# Design-TSC.net
KiCad netlist of a schematic drawn in EAGLE
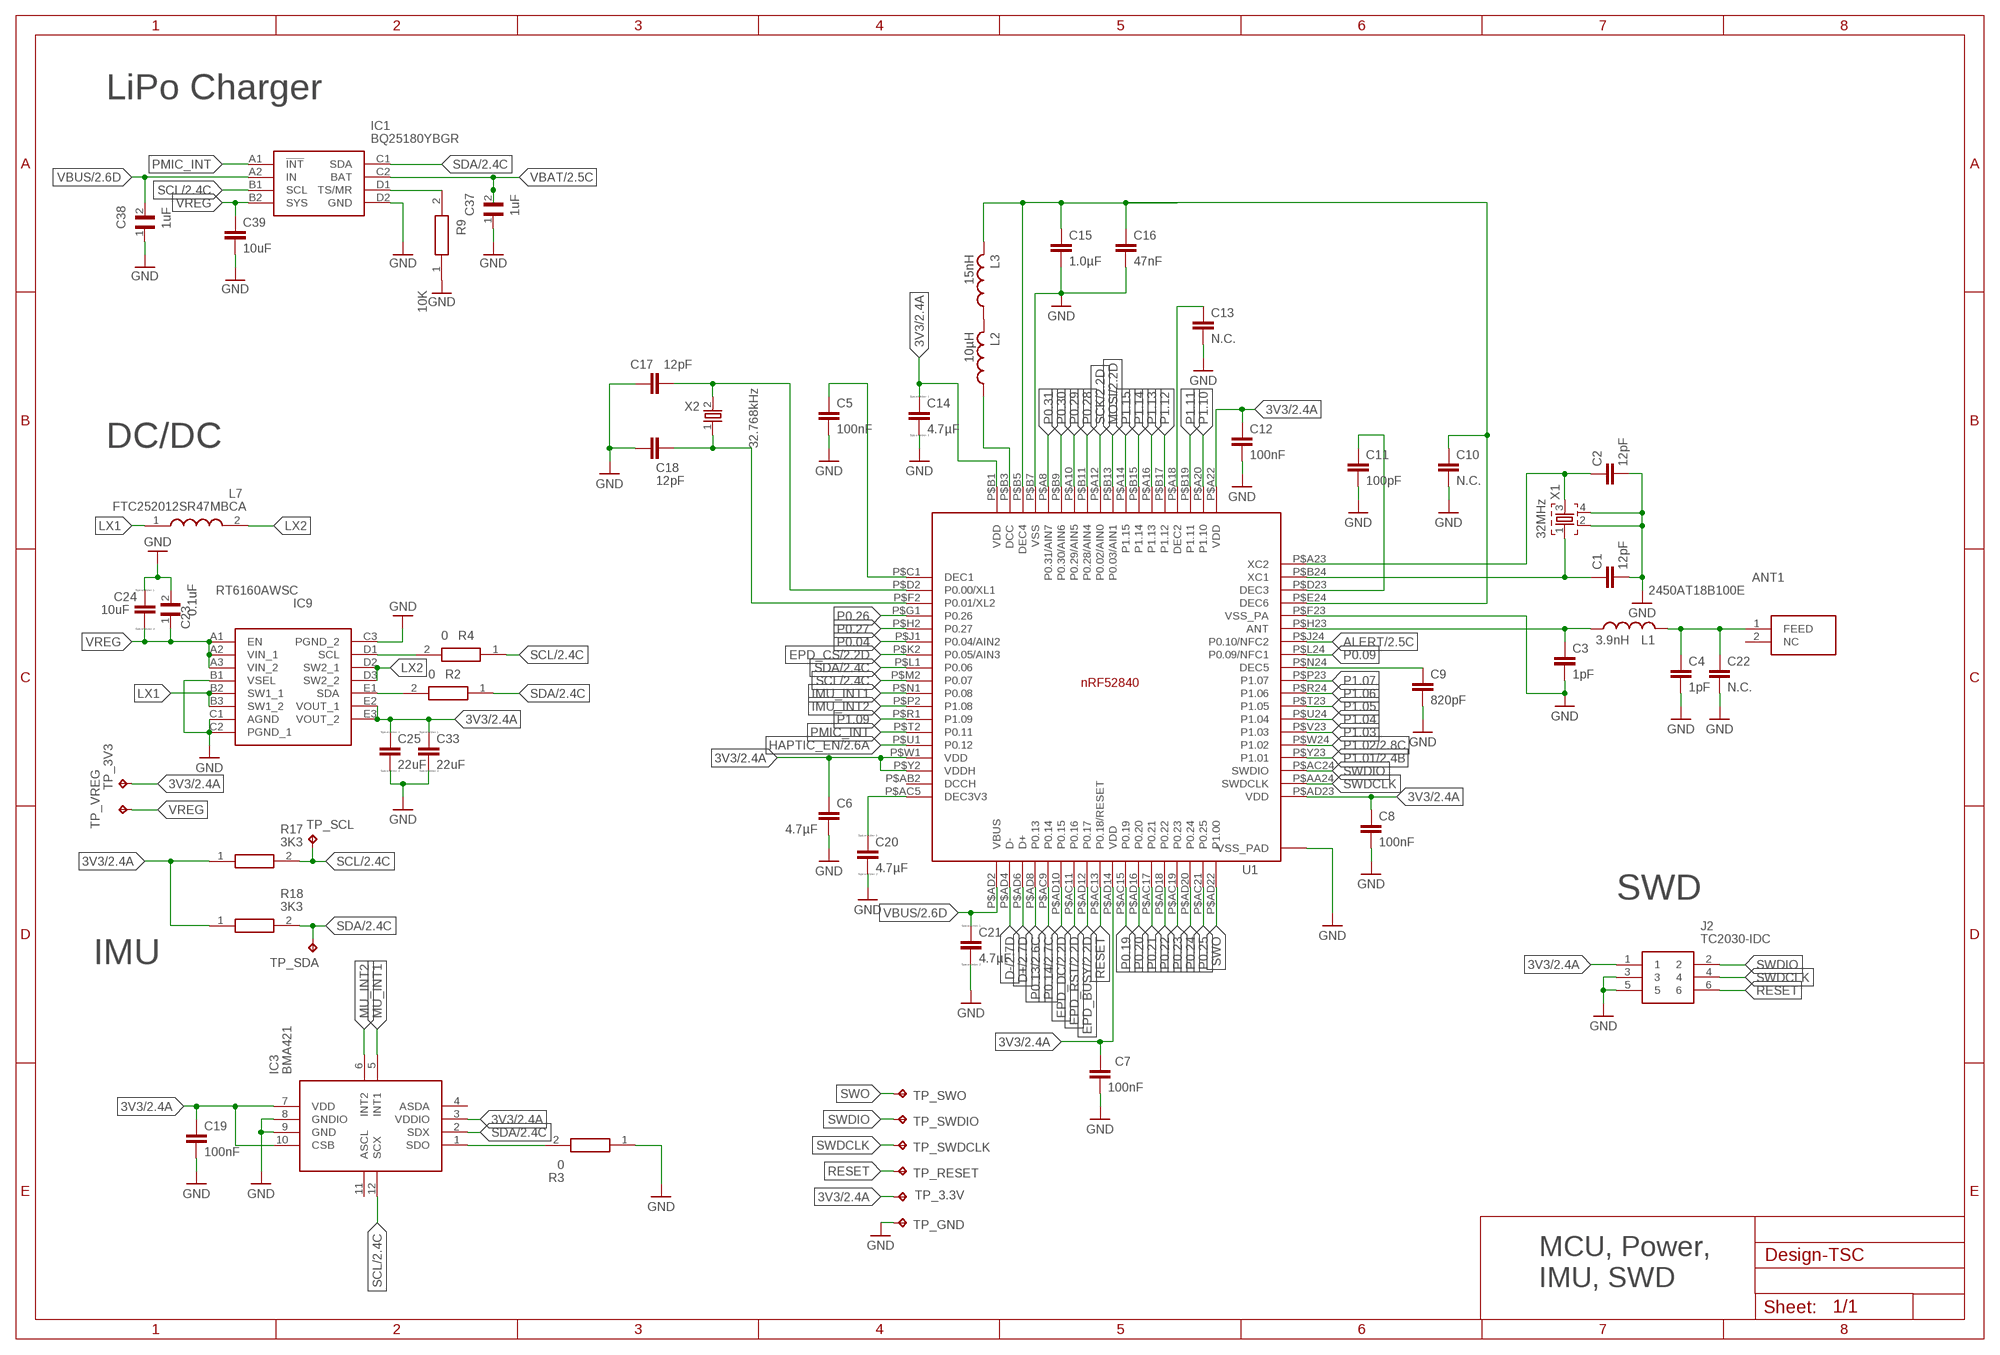
[diagram p0: schematic, sheet 1, part 1 of 2]
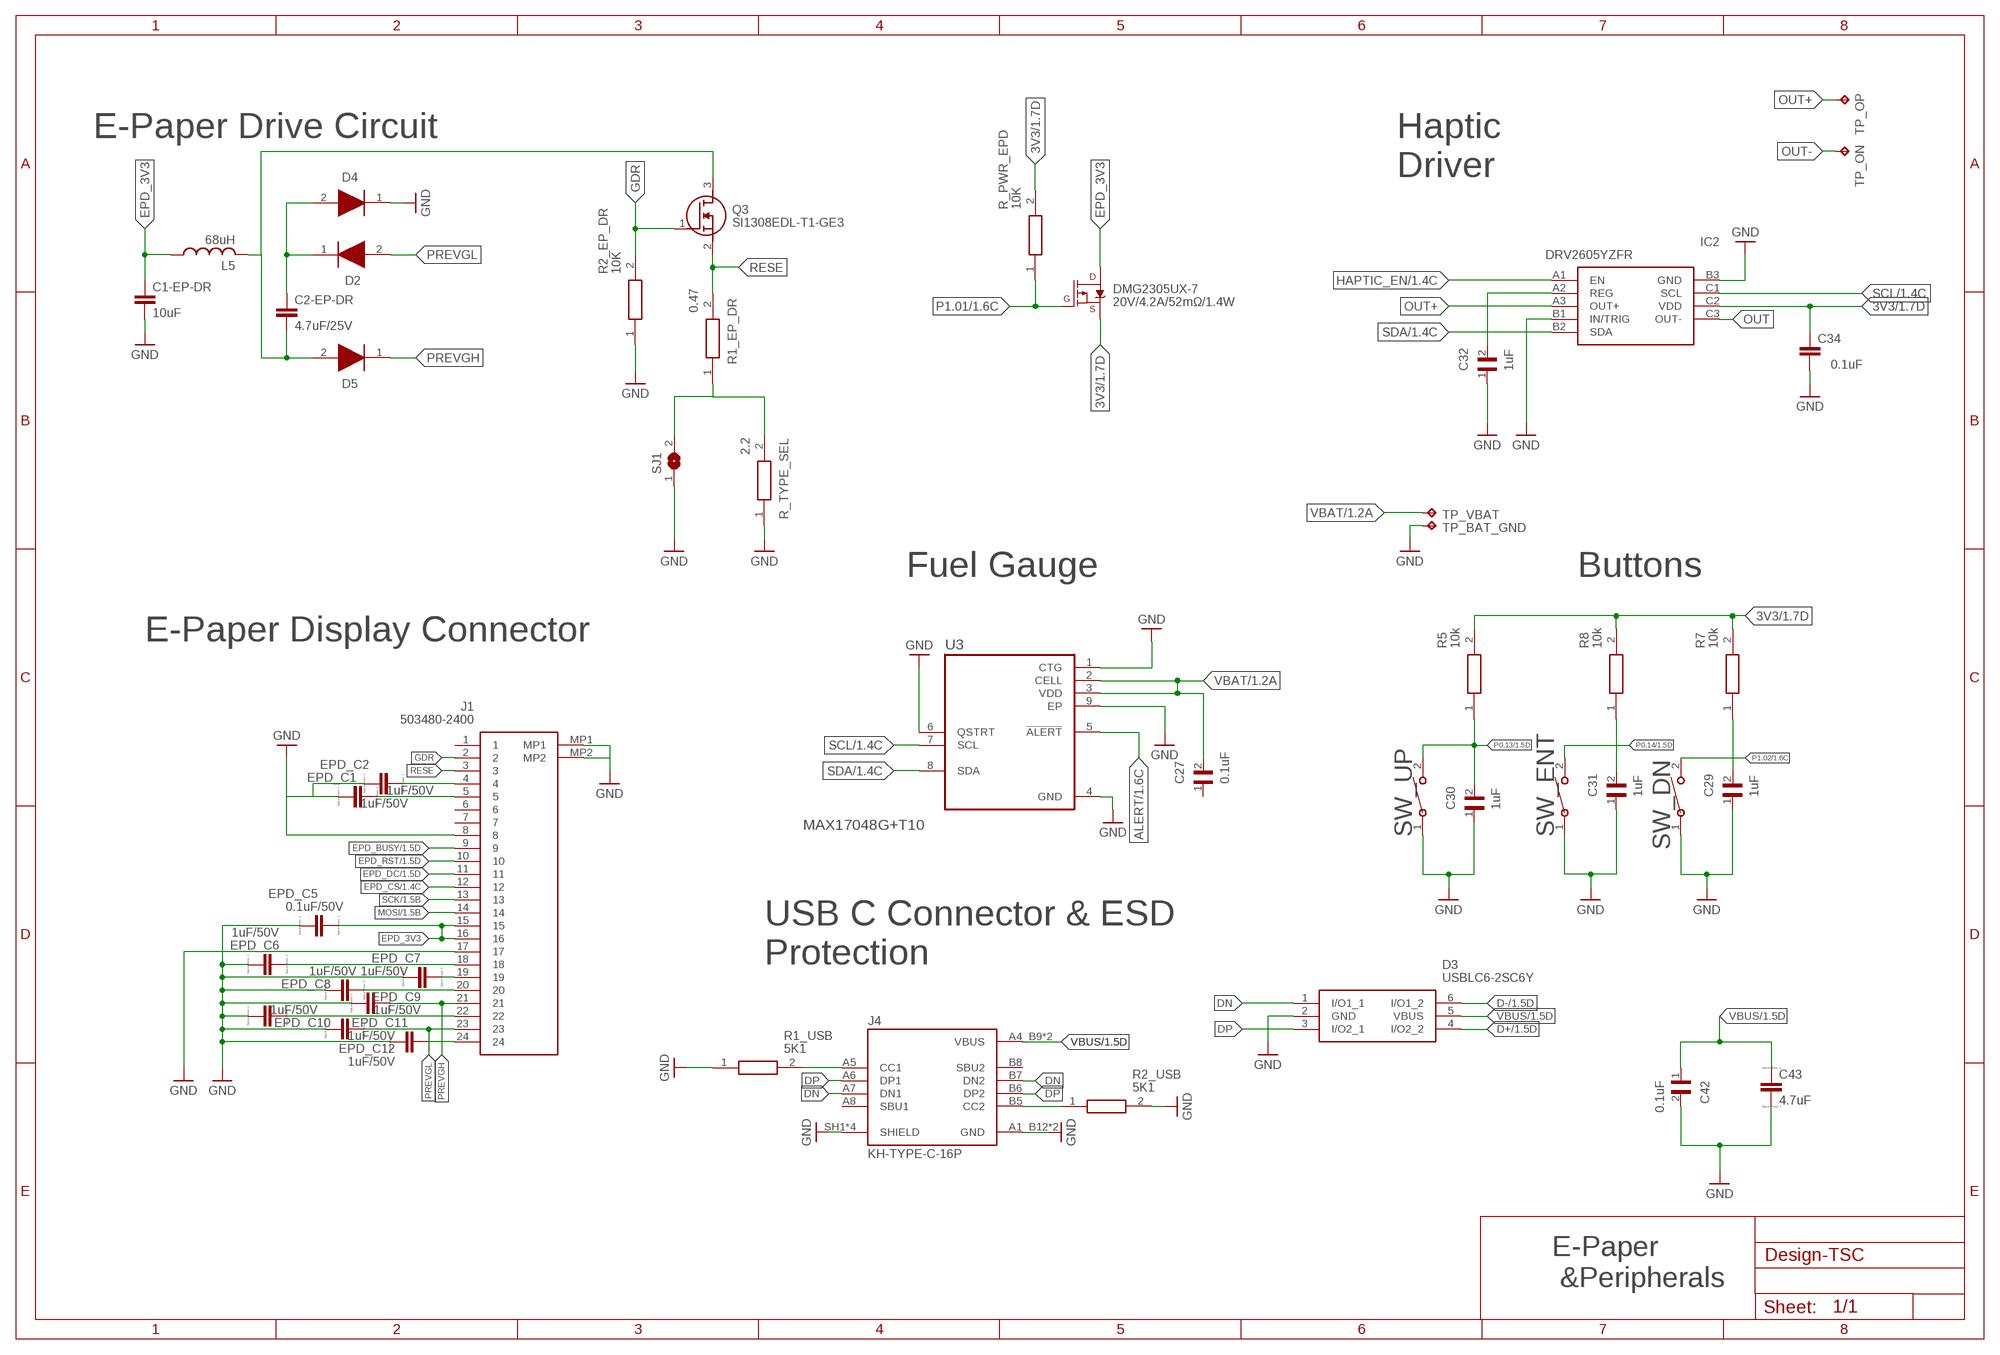
[diagram p1: schematic, sheet 1, part 2 of 2]

(export (version "E")
  (design (tool "Eeschema 10.0.6"))
  (components
    (comp (ref "ANT1")
      (value "2450AT18B100E")
      (footprint "eagle-import:2450AT18B100E_ANTC3216X140N")
      (fields (field (name "MOUSER_PART_NUMBER") "609-2450AT18B100E"))
      (libsource (lib "eagle-import") (part "2450AT18B100E_2450AT18B100E"))
    )
    (comp (ref "C1")
      (value "12pF")
      (footprint "eagle-import:NORDIC_NRF_3_RESC0201_L")
      (libsource (lib "eagle-import") (part "NORDIC_NRF_3_CAPACITOR_0201_L"))
    )
    (comp (ref "C1-EP-DR")
      (value "10uF")
      (footprint "eagle-import:NORDIC_NRF_3_RESC0201_L")
      (libsource (lib "eagle-import") (part "NORDIC_NRF_3_CAPACITOR_0201_L"))
    )
    (comp (ref "C2")
      (value "12pF")
      (footprint "eagle-import:NORDIC_NRF_3_RESC0201_L")
      (libsource (lib "eagle-import") (part "NORDIC_NRF_3_CAPACITOR_0201_L"))
    )
    (comp (ref "C2-EP-DR")
      (value "4.7uF/25V")
      (footprint "eagle-import:NORDIC_NRF_3_RESC0201_L")
      (libsource (lib "eagle-import") (part "NORDIC_NRF_3_CAPACITOR_0201_L"))
    )
    (comp (ref "C3")
      (value "1pF")
      (footprint "eagle-import:NORDIC_NRF_3_RESC0201_L")
      (libsource (lib "eagle-import") (part "NORDIC_NRF_3_CAPACITOR_0201_L"))
    )
    (comp (ref "C4")
      (value "1pF")
      (footprint "eagle-import:NORDIC_NRF_3_RESC0201_L")
      (libsource (lib "eagle-import") (part "NORDIC_NRF_3_CAPACITOR_0201_L"))
    )
    (comp (ref "C5")
      (value "100nF")
      (footprint "eagle-import:NORDIC_NRF_3_RESC0201_L")
      (libsource (lib "eagle-import") (part "NORDIC_NRF_3_CAPACITOR_0201_L"))
    )
    (comp (ref "C6")
      (value "4.7µF")
      (footprint "eagle-import:NORDIC_NRF_3_RESC0201_L")
      (libsource (lib "eagle-import") (part "NORDIC_NRF_3_CAPACITOR_0201_L"))
    )
    (comp (ref "C7")
      (value "100nF")
      (footprint "eagle-import:NORDIC_NRF_3_RESC0201_L")
      (libsource (lib "eagle-import") (part "NORDIC_NRF_3_CAPACITOR_0201_L"))
    )
    (comp (ref "C8")
      (value "100nF")
      (footprint "eagle-import:NORDIC_NRF_3_RESC0201_L")
      (libsource (lib "eagle-import") (part "NORDIC_NRF_3_CAPACITOR_0201_L"))
    )
    (comp (ref "C9")
      (value "820pF")
      (footprint "eagle-import:NORDIC_NRF_3_RESC0201_L")
      (libsource (lib "eagle-import") (part "NORDIC_NRF_3_CAPACITOR_0201_L"))
    )
    (comp (ref "C10")
      (value "N.C.")
      (footprint "eagle-import:NORDIC_NRF_3_RESC0201_L")
      (libsource (lib "eagle-import") (part "NORDIC_NRF_3_CAPACITOR_0201_L"))
    )
    (comp (ref "C11")
      (value "100pF")
      (footprint "eagle-import:NORDIC_NRF_3_RESC0201_L")
      (libsource (lib "eagle-import") (part "NORDIC_NRF_3_CAPACITOR_0201_L"))
    )
    (comp (ref "C12")
      (value "100nF")
      (footprint "eagle-import:NORDIC_NRF_3_RESC0201_L")
      (libsource (lib "eagle-import") (part "NORDIC_NRF_3_CAPACITOR_0201_L"))
    )
    (comp (ref "C13")
      (value "N.C.")
      (footprint "eagle-import:NORDIC_NRF_3_RESC0201_L")
      (libsource (lib "eagle-import") (part "NORDIC_NRF_3_CAPACITOR_0201_L"))
    )
    (comp (ref "C14")
      (value "4.7µF")
      (footprint "eagle-import:ESP32_C6_LIBRARY_1_ESP32_WROVER_EAGLE-LTSPICE_C0402")
      (libsource (lib "eagle-import") (part "ESP32_C6_LIBRARY_1_ESP32_WROVER_EAGLE-LTSPICE_CC0402"))
    )
    (comp (ref "C15")
      (value "1.0µF")
      (footprint "eagle-import:NORDIC_NRF_3_RESC0201_L")
      (libsource (lib "eagle-import") (part "NORDIC_NRF_3_CAPACITOR_0201_L"))
    )
    (comp (ref "C16")
      (value "47nF")
      (footprint "eagle-import:NORDIC_NRF_3_RESC0201_L")
      (libsource (lib "eagle-import") (part "NORDIC_NRF_3_CAPACITOR_0201_L"))
    )
    (comp (ref "C17")
      (value "12pF")
      (footprint "eagle-import:NORDIC_NRF_3_RESC0201_L")
      (libsource (lib "eagle-import") (part "NORDIC_NRF_3_CAPACITOR_0201_L"))
    )
    (comp (ref "C18")
      (value "12pF")
      (footprint "eagle-import:NORDIC_NRF_3_RESC0201_L")
      (libsource (lib "eagle-import") (part "NORDIC_NRF_3_CAPACITOR_0201_L"))
    )
    (comp (ref "C19")
      (value "100nF")
      (footprint "eagle-import:NORDIC_NRF_3_RESC0201_L")
      (libsource (lib "eagle-import") (part "NORDIC_NRF_3_CAPACITOR_0201_L"))
    )
    (comp (ref "C20")
      (value "4.7µF")
      (footprint "eagle-import:ESP32_C6_LIBRARY_1_ESP32_WROVER_EAGLE-LTSPICE_C0402")
      (libsource (lib "eagle-import") (part "ESP32_C6_LIBRARY_1_ESP32_WROVER_EAGLE-LTSPICE_CC0402"))
    )
    (comp (ref "C21")
      (value "4.7µF")
      (footprint "eagle-import:ESP32_C6_LIBRARY_1_ESP32_WROVER_EAGLE-LTSPICE_C0402")
      (libsource (lib "eagle-import") (part "ESP32_C6_LIBRARY_1_ESP32_WROVER_EAGLE-LTSPICE_CC0402"))
    )
    (comp (ref "C22")
      (value "N.C.")
      (footprint "eagle-import:NORDIC_NRF_3_RESC0201_L")
      (libsource (lib "eagle-import") (part "NORDIC_NRF_3_CAPACITOR_0201_L"))
    )
    (comp (ref "C23")
      (value "0.1uF")
      (footprint "eagle-import:GRM011R60J152KE01L_2_CAPC0201X13N")
      (fields (field (name "MF") "Murata") (field (name "MP") "GRM011R60J152KE01L"))
      (libsource (lib "eagle-import") (part "GRM011R60J152KE01L_2_GRM011R60J152KE01L"))
    )
    (comp (ref "C24")
      (value "10uF")
      (footprint "eagle-import:ESP32_C6_LIBRARY_1_ESP32_WROVER_EAGLE-LTSPICE_C0402")
      (libsource (lib "eagle-import") (part "ESP32_C6_LIBRARY_1_ESP32_WROVER_EAGLE-LTSPICE_CC0402"))
    )
    (comp (ref "C25")
      (value "22uF")
      (footprint "eagle-import:ESP32_C6_LIBRARY_1_ESP32_WROVER_EAGLE-LTSPICE_C0402")
      (libsource (lib "eagle-import") (part "ESP32_C6_LIBRARY_1_ESP32_WROVER_EAGLE-LTSPICE_CC0402"))
    )
    (comp (ref "C27")
      (value "0.1uF")
      (footprint "eagle-import:GRM011R60J152KE01L_2_CAPC0201X13N")
      (fields (field (name "MF") "Murata") (field (name "MP") "GRM011R60J152KE01L"))
      (libsource (lib "eagle-import") (part "GRM011R60J152KE01L_2_GRM011R60J152KE01L"))
    )
    (comp (ref "C29")
      (value "1uF")
      (footprint "eagle-import:GRM011R60J152KE01L_2_CAPC0201X13N")
      (fields (field (name "MF") "Murata") (field (name "MP") "GRM011R60J152KE01L"))
      (libsource (lib "eagle-import") (part "GRM011R60J152KE01L_2_GRM011R60J152KE01L"))
    )
    (comp (ref "C30")
      (value "1uF")
      (footprint "eagle-import:GRM011R60J152KE01L_2_CAPC0201X13N")
      (fields (field (name "MF") "Murata") (field (name "MP") "GRM011R60J152KE01L"))
      (libsource (lib "eagle-import") (part "GRM011R60J152KE01L_2_GRM011R60J152KE01L"))
    )
    (comp (ref "C31")
      (value "1uF")
      (footprint "eagle-import:GRM011R60J152KE01L_2_CAPC0201X13N")
      (fields (field (name "MF") "Murata") (field (name "MP") "GRM011R60J152KE01L"))
      (libsource (lib "eagle-import") (part "GRM011R60J152KE01L_2_GRM011R60J152KE01L"))
    )
    (comp (ref "C32")
      (value "1uF")
      (footprint "eagle-import:GRM011R60J152KE01L_2_CAPC0201X13N")
      (fields (field (name "MF") "Murata") (field (name "MP") "GRM011R60J152KE01L"))
      (libsource (lib "eagle-import") (part "GRM011R60J152KE01L_2_GRM011R60J152KE01L"))
    )
    (comp (ref "C33")
      (value "22uF")
      (footprint "eagle-import:ESP32_C6_LIBRARY_1_ESP32_WROVER_EAGLE-LTSPICE_C0402")
      (libsource (lib "eagle-import") (part "ESP32_C6_LIBRARY_1_ESP32_WROVER_EAGLE-LTSPICE_CC0402"))
    )
    (comp (ref "C34")
      (value "0.1uF")
      (footprint "eagle-import:NORDIC_NRF_3_RESC0201_L")
      (libsource (lib "eagle-import") (part "NORDIC_NRF_3_CAPACITOR_0201_L"))
    )
    (comp (ref "C37")
      (value "1uF")
      (footprint "eagle-import:GRM011R60J152KE01L_2_CAPC0201X13N")
      (fields (field (name "MF") "Murata") (field (name "MP") "GRM011R60J152KE01L"))
      (libsource (lib "eagle-import") (part "GRM011R60J152KE01L_2_GRM011R60J152KE01L"))
    )
    (comp (ref "C38")
      (value "1uF")
      (footprint "eagle-import:GRM011R60J152KE01L_2_CAPC0201X13N")
      (fields (field (name "MF") "Murata") (field (name "MP") "GRM011R60J152KE01L"))
      (libsource (lib "eagle-import") (part "GRM011R60J152KE01L_2_GRM011R60J152KE01L"))
    )
    (comp (ref "C39")
      (value "10uF")
      (footprint "eagle-import:NORDIC_NRF_3_RESC0201_L")
      (libsource (lib "eagle-import") (part "NORDIC_NRF_3_CAPACITOR_0201_L"))
    )
    (comp (ref "C42")
      (value "0.1uF")
      (footprint "eagle-import:GRM011R60J152KE01L_2_CAPC0201X13N")
      (fields (field (name "MF") "Murata") (field (name "MP") "GRM011R60J152KE01L"))
      (libsource (lib "eagle-import") (part "GRM011R60J152KE01L_2_GRM011R60J152KE01L"))
    )
    (comp (ref "C43")
      (value "4.7uF")
      (footprint "eagle-import:ESP32_C6_LIBRARY_1_ESP32_WROVER_EAGLE-LTSPICE_C0402")
      (libsource (lib "eagle-import") (part "ESP32_C6_LIBRARY_1_ESP32_WROVER_EAGLE-LTSPICE_CC0402"))
    )
    (comp (ref "D2")
      (value "ESP32_C6_LIBRARY_5_MBR0530")
      (footprint "eagle-import:ESP32_C6_LIBRARY_5_SOD3716X135N")
      (fields (field (name "MF") "ON Semiconductor") (field (name "MP") "MBR0530"))
      (libsource (lib "eagle-import") (part "ESP32_C6_LIBRARY_5_MBR0530"))
    )
    (comp (ref "D3")
      (value "USBLC6-2SC6Y")
      (footprint "eagle-import:ESP32_C6_LIBRARY_3_SOT95P280X145-6N")
      (fields (field (name "MF") "STMicroelectronics"))
      (libsource (lib "eagle-import") (part "ESP32_C6_LIBRARY_3_USBLC6-2SC6Y"))
    )
    (comp (ref "D4")
      (value "ESP32_C6_LIBRARY_5_MBR0530")
      (footprint "eagle-import:ESP32_C6_LIBRARY_5_SOD3716X135N")
      (fields (field (name "MF") "ON Semiconductor") (field (name "MP") "MBR0530"))
      (libsource (lib "eagle-import") (part "ESP32_C6_LIBRARY_5_MBR0530"))
    )
    (comp (ref "D5")
      (value "ESP32_C6_LIBRARY_5_MBR0530")
      (footprint "eagle-import:ESP32_C6_LIBRARY_5_SOD3716X135N")
      (fields (field (name "MF") "ON Semiconductor") (field (name "MP") "MBR0530"))
      (libsource (lib "eagle-import") (part "ESP32_C6_LIBRARY_5_MBR0530"))
    )
    (comp (ref "DMG2305UX-7")
      (value "20V/4.2A/52mΩ/1.4W")
      (footprint "eagle-import:ESP32_C6_LIBRARY_4_ESP32_C6_LIBRARY_4_ESP32_C6_LIBRARY_4_ESP32_C6_LIBRARY_4_ESP32_WROVER_SPARKFUN-DISCRETESEMI_SOT23-3")
      (libsource (lib "eagle-import") (part "ESP32_C6_LIBRARY_4_ESP32_WROVER_SPARKFUN-DISCRETESEMI_MOSFET_PCH-DMG2305UX-7"))
    )
    (comp (ref "EPD_C1")
      (value "1uF/50V")
      (footprint "eagle-import:ESP32_C6_LIBRARY_1_ESP32_WROVER_EAGLE-LTSPICE_C0402")
      (libsource (lib "eagle-import") (part "ESP32_C6_LIBRARY_1_ESP32_WROVER_EAGLE-LTSPICE_CC0402"))
    )
    (comp (ref "EPD_C2")
      (value "1uF/50V")
      (footprint "eagle-import:ESP32_C6_LIBRARY_1_ESP32_WROVER_EAGLE-LTSPICE_C0402")
      (libsource (lib "eagle-import") (part "ESP32_C6_LIBRARY_1_ESP32_WROVER_EAGLE-LTSPICE_CC0402"))
    )
    (comp (ref "EPD_C5")
      (value "0.1uF/50V")
      (footprint "eagle-import:ESP32_C6_LIBRARY_1_ESP32_WROVER_EAGLE-LTSPICE_C0402")
      (libsource (lib "eagle-import") (part "ESP32_C6_LIBRARY_1_ESP32_WROVER_EAGLE-LTSPICE_CC0402"))
    )
    (comp (ref "EPD_C6")
      (value "1uF/50V")
      (footprint "eagle-import:ESP32_C6_LIBRARY_1_ESP32_WROVER_EAGLE-LTSPICE_C0402")
      (libsource (lib "eagle-import") (part "ESP32_C6_LIBRARY_1_ESP32_WROVER_EAGLE-LTSPICE_CC0402"))
    )
    (comp (ref "EPD_C7")
      (value "1uF/50V")
      (footprint "eagle-import:ESP32_C6_LIBRARY_1_ESP32_WROVER_EAGLE-LTSPICE_C0402")
      (libsource (lib "eagle-import") (part "ESP32_C6_LIBRARY_1_ESP32_WROVER_EAGLE-LTSPICE_CC0402"))
    )
    (comp (ref "EPD_C8")
      (value "1uF/50V")
      (footprint "eagle-import:ESP32_C6_LIBRARY_1_ESP32_WROVER_EAGLE-LTSPICE_C0402")
      (libsource (lib "eagle-import") (part "ESP32_C6_LIBRARY_1_ESP32_WROVER_EAGLE-LTSPICE_CC0402"))
    )
    (comp (ref "EPD_C9")
      (value "1uF/50V")
      (footprint "eagle-import:ESP32_C6_LIBRARY_1_ESP32_WROVER_EAGLE-LTSPICE_C0402")
      (libsource (lib "eagle-import") (part "ESP32_C6_LIBRARY_1_ESP32_WROVER_EAGLE-LTSPICE_CC0402"))
    )
    (comp (ref "EPD_C10")
      (value "1uF/50V")
      (footprint "eagle-import:ESP32_C6_LIBRARY_1_ESP32_WROVER_EAGLE-LTSPICE_C0402")
      (libsource (lib "eagle-import") (part "ESP32_C6_LIBRARY_1_ESP32_WROVER_EAGLE-LTSPICE_CC0402"))
    )
    (comp (ref "EPD_C11")
      (value "1uF/50V")
      (footprint "eagle-import:ESP32_C6_LIBRARY_1_ESP32_WROVER_EAGLE-LTSPICE_C0402")
      (libsource (lib "eagle-import") (part "ESP32_C6_LIBRARY_1_ESP32_WROVER_EAGLE-LTSPICE_CC0402"))
    )
    (comp (ref "EPD_C12")
      (value "1uF/50V")
      (footprint "eagle-import:ESP32_C6_LIBRARY_1_ESP32_WROVER_EAGLE-LTSPICE_C0402")
      (libsource (lib "eagle-import") (part "ESP32_C6_LIBRARY_1_ESP32_WROVER_EAGLE-LTSPICE_CC0402"))
    )
    (comp (ref "IC1")
      (value "BQ25180YBGR")
      (footprint "eagle-import:BQ25180YBGR_BGA8C40P2X4_100X155X50")
      (fields (field (name "MOUSER_PART_NUMBER") "595-BQ25180YBGR"))
      (libsource (lib "eagle-import") (part "BQ25180YBGR_BQ25180YBGR"))
    )
    (comp (ref "IC2")
      (value "DRV2605YZFR")
      (footprint "eagle-import:DRV2605YZFR_BGA9C50P3X3_144X144X62")
      (libsource (lib "eagle-import") (part "DRV2605YZFR_DRV2605YZFR"))
    )
    (comp (ref "IC3")
      (value "BMA421")
      (footprint "eagle-import:BMA423_BMA423")
      (fields (field (name "ARROW_PART_NUMBER") "BMA423") (field (name "MOUSER_PART_NUMBER") "262-BMA423"))
      (libsource (lib "eagle-import") (part "BMA423_BMA423"))
    )
    (comp (ref "IC9")
      (value "RT6160AWSC")
      (footprint "eagle-import:RT6160AWSC_BGA15C40P3X5_140X230X60")
      (fields (field (name "MOUSER_PART_NUMBER") "835-RT6160AWSC"))
      (libsource (lib "eagle-import") (part "RT6160AWSC_RT6160AWSC"))
    )
    (comp (ref "J1")
      (value "503480-2400")
      (footprint "eagle-import:503480-2400_5034802400")
      (fields (field (name "MOUSER_PART_NUMBER") "538-503480-2400"))
      (libsource (lib "eagle-import") (part "503480-2400_503480-2400"))
    )
    (comp (ref "J2")
      (value "TC2030-IDC")
      (footprint "eagle-import:TC2030-IDC_TC2030IDC")
      (libsource (lib "eagle-import") (part "TC2030-IDC_TC2030-IDC"))
    )
    (comp (ref "J4")
      (value "KH-TYPE-C-16P")
      (footprint "eagle-import:KH-TYPE-C-16P_KINGHELM_KH-TYPE-C-16P")
      (fields (field (name "MF") "kinghelm"))
      (libsource (lib "eagle-import") (part "KH-TYPE-C-16P_KH-TYPE-C-16P"))
    )
    (comp (ref "L1")
      (value "3.9nH")
      (footprint "eagle-import:NORDIC_NRF_2_RESC0402_L")
      (libsource (lib "eagle-import") (part "NORDIC_NRF_2_INDUCTOR_0402_L"))
    )
    (comp (ref "L2")
      (value "10µH")
      (footprint "eagle-import:NORDIC_NRF_2_RESC0402_L")
      (libsource (lib "eagle-import") (part "NORDIC_NRF_2_INDUCTOR_0402_L"))
    )
    (comp (ref "L3")
      (value "15nH")
      (footprint "eagle-import:NORDIC_NRF_2_RESC0402_L")
      (libsource (lib "eagle-import") (part "NORDIC_NRF_2_INDUCTOR_0402_L"))
    )
    (comp (ref "L5")
      (value "68uH")
      (footprint "eagle-import:NORDIC_NRF_2_RESC0402_L")
      (libsource (lib "eagle-import") (part "NORDIC_NRF_2_INDUCTOR_0402_L"))
    )
    (comp (ref "L7")
      (value "FTC252012SR47MBCA")
      (footprint "eagle-import:MLP2016SR47MT0S1_INDC2016X100N")
      (libsource (lib "eagle-import") (part "MLP2016SR47MT0S1_FTC252012SR47MBCA"))
    )
    (comp (ref "Q3")
      (value "SI1308EDL-T1-GE3")
      (footprint "eagle-import:ESP32_C6_LIBRARY_6_SOT65P210X110-3N")
      (fields (field (name "MF") "Vishay Siliconix"))
      (libsource (lib "eagle-import") (part "ESP32_C6_LIBRARY_6_SI1308EDL-T1-GE3"))
    )
    (comp (ref "R1_EP_DR")
      (value "0.47")
      (footprint "eagle-import:ERA-1AEB3401C_0201")
      (libsource (lib "eagle-import") (part "ERA-1AEB3401C_CPF0201D7K68C1"))
    )
    (comp (ref "R1_USB")
      (value "5K1")
      (footprint "eagle-import:CPF0201D7K68C1_0201")
      (libsource (lib "eagle-import") (part "CPF0201D7K68C1_CPF0201D7K68C1"))
    )
    (comp (ref "R2")
      (value "0")
      (footprint "eagle-import:CPF0201D7K68C1_0201")
      (libsource (lib "eagle-import") (part "CPF0201D7K68C1_CPF0201D7K68C1"))
    )
    (comp (ref "R2_EP_DR")
      (value "10K")
      (footprint "eagle-import:ERA-1AEB3401C_0201")
      (libsource (lib "eagle-import") (part "ERA-1AEB3401C_CPF0201D7K68C1"))
    )
    (comp (ref "R2_USB")
      (value "5K1")
      (footprint "eagle-import:ERA-1AEB3401C_0201")
      (libsource (lib "eagle-import") (part "ERA-1AEB3401C_CPF0201D7K68C1"))
    )
    (comp (ref "R3")
      (value "0")
      (footprint "eagle-import:ERA-1AEB3401C_0201")
      (libsource (lib "eagle-import") (part "ERA-1AEB3401C_CPF0201D7K68C1"))
    )
    (comp (ref "R4")
      (value "0")
      (footprint "eagle-import:CPF0201D7K68C1_0201")
      (libsource (lib "eagle-import") (part "CPF0201D7K68C1_CPF0201D7K68C1"))
    )
    (comp (ref "R5")
      (value "10k")
      (footprint "eagle-import:CPF0201D7K68C1_0201")
      (libsource (lib "eagle-import") (part "CPF0201D7K68C1_CPF0201D7K68C1"))
    )
    (comp (ref "R7")
      (value "10k")
      (footprint "eagle-import:CPF0201D7K68C1_0201")
      (libsource (lib "eagle-import") (part "CPF0201D7K68C1_CPF0201D7K68C1"))
    )
    (comp (ref "R8")
      (value "10k")
      (footprint "eagle-import:CPF0201D7K68C1_0201")
      (libsource (lib "eagle-import") (part "CPF0201D7K68C1_CPF0201D7K68C1"))
    )
    (comp (ref "R9")
      (value "10K")
      (footprint "eagle-import:ERA-1AEB3401C_0201")
      (libsource (lib "eagle-import") (part "ERA-1AEB3401C_CPF0201D7K68C1"))
    )
    (comp (ref "R17")
      (value "3K3")
      (footprint "eagle-import:CPF0201D7K68C1_0201")
      (libsource (lib "eagle-import") (part "CPF0201D7K68C1_CPF0201D7K68C1"))
    )
    (comp (ref "R18")
      (value "3K3")
      (footprint "eagle-import:CPF0201D7K68C1_0201")
      (libsource (lib "eagle-import") (part "CPF0201D7K68C1_CPF0201D7K68C1"))
    )
    (comp (ref "R_PWR_EPD")
      (value "10K")
      (footprint "eagle-import:CPF0201D7K68C1_0201")
      (libsource (lib "eagle-import") (part "CPF0201D7K68C1_CPF0201D7K68C1"))
    )
    (comp (ref "R_TYPE_SEL")
      (value "2.2")
      (footprint "eagle-import:ERA-1AEB3401C_0201")
      (libsource (lib "eagle-import") (part "ERA-1AEB3401C_CPF0201D7K68C1"))
    )
    (comp (ref "SJ1")
      (value "ESP32_C6_LIBRARY_7_JUMPER_SJ")
      (footprint "eagle-import:ESP32_C6_LIBRARY_7_JUMPER_SJ")
      (libsource (lib "eagle-import") (part "ESP32_C6_LIBRARY_7_JUMPER_SJ"))
    )
    (comp (ref "SW_DN")
      (value "2025-10-22_07-23-44_LIBRARY_EVP-AKE31ASW_EVP-AKE31A_PAN")
      (footprint "eagle-import:2025-10-22_07-23-44_LIBRARY_SW_EVP-AKE31A_PAN")
      (fields
        (field (name "MANUFACTURER_PART_NUMBER") "EVP-AKE31A")
        (field (name "COPYRIGHT") "Copyright (C) 2025 Ultra Librarian. All rights reserved.")
      )
      (libsource (lib "eagle-import") (part "2025-10-22_07-23-44_LIBRARY_EVP-AKE31ASW_EVP-AKE31A_PAN"))
    )
    (comp (ref "SW_ENT")
      (value "2025-10-22_07-23-44_LIBRARY_EVP-AKE31ASW_EVP-AKE31A_PAN")
      (footprint "eagle-import:2025-10-22_07-23-44_LIBRARY_SW_EVP-AKE31A_PAN")
      (fields
        (field (name "MANUFACTURER_PART_NUMBER") "EVP-AKE31A")
        (field (name "COPYRIGHT") "Copyright (C) 2025 Ultra Librarian. All rights reserved.")
      )
      (libsource (lib "eagle-import") (part "2025-10-22_07-23-44_LIBRARY_EVP-AKE31ASW_EVP-AKE31A_PAN"))
    )
    (comp (ref "SW_UP")
      (value "2025-10-22_07-23-44_LIBRARY_EVP-AKE31ASW_EVP-AKE31A_PAN")
      (footprint "eagle-import:2025-10-22_07-23-44_LIBRARY_SW_EVP-AKE31A_PAN")
      (fields
        (field (name "MANUFACTURER_PART_NUMBER") "EVP-AKE31A")
        (field (name "COPYRIGHT") "Copyright (C) 2025 Ultra Librarian. All rights reserved.")
      )
      (libsource (lib "eagle-import") (part "2025-10-22_07-23-44_LIBRARY_EVP-AKE31ASW_EVP-AKE31A_PAN"))
    )
    (comp (ref "TP_3.3V")
      (value "HECTOR_WATCH_1_TPTP20R")
      (footprint "eagle-import:HECTOR_WATCH_1_TP20R")
      (libsource (lib "eagle-import") (part "HECTOR_WATCH_1_TPTP20R"))
    )
    (comp (ref "TP_3V3")
      (value "HECTOR_WATCH_1_TPTP20R")
      (footprint "eagle-import:HECTOR_WATCH_1_TP20R")
      (libsource (lib "eagle-import") (part "HECTOR_WATCH_1_TPTP20R"))
    )
    (comp (ref "TP_BAT_GND")
      (value "HECTOR_WATCH_1_TPTP20R")
      (footprint "eagle-import:HECTOR_WATCH_1_TP20R")
      (libsource (lib "eagle-import") (part "HECTOR_WATCH_1_TPTP20R"))
    )
    (comp (ref "TP_GND")
      (value "HECTOR_WATCH_1_TPTP20R")
      (footprint "eagle-import:HECTOR_WATCH_1_TP20R")
      (libsource (lib "eagle-import") (part "HECTOR_WATCH_1_TPTP20R"))
    )
    (comp (ref "TP_ON")
      (value "HECTOR_WATCH_1_TPTP20R")
      (footprint "eagle-import:HECTOR_WATCH_1_TP20R")
      (libsource (lib "eagle-import") (part "HECTOR_WATCH_1_TPTP20R"))
    )
    (comp (ref "TP_OP")
      (value "HECTOR_WATCH_1_TPTP20R")
      (footprint "eagle-import:HECTOR_WATCH_1_TP20R")
      (libsource (lib "eagle-import") (part "HECTOR_WATCH_1_TPTP20R"))
    )
    (comp (ref "TP_RESET")
      (value "HECTOR_WATCH_1_TPTP20R")
      (footprint "eagle-import:HECTOR_WATCH_1_TP20R")
      (libsource (lib "eagle-import") (part "HECTOR_WATCH_1_TPTP20R"))
    )
    (comp (ref "TP_SCL")
      (value "HECTOR_WATCH_1_TPTP20R")
      (footprint "eagle-import:HECTOR_WATCH_1_TP20R")
      (libsource (lib "eagle-import") (part "HECTOR_WATCH_1_TPTP20R"))
    )
    (comp (ref "TP_SDA")
      (value "HECTOR_WATCH_1_TPTP20R")
      (footprint "eagle-import:HECTOR_WATCH_1_TP20R")
      (libsource (lib "eagle-import") (part "HECTOR_WATCH_1_TPTP20R"))
    )
    (comp (ref "TP_SWDCLK")
      (value "HECTOR_WATCH_1_TPTP20R")
      (footprint "eagle-import:HECTOR_WATCH_1_TP20R")
      (libsource (lib "eagle-import") (part "HECTOR_WATCH_1_TPTP20R"))
    )
    (comp (ref "TP_SWDIO")
      (value "HECTOR_WATCH_1_TPTP20R")
      (footprint "eagle-import:HECTOR_WATCH_1_TP20R")
      (libsource (lib "eagle-import") (part "HECTOR_WATCH_1_TPTP20R"))
    )
    (comp (ref "TP_SWO")
      (value "HECTOR_WATCH_1_TPTP20R")
      (footprint "eagle-import:HECTOR_WATCH_1_TP20R")
      (libsource (lib "eagle-import") (part "HECTOR_WATCH_1_TPTP20R"))
    )
    (comp (ref "TP_VBAT")
      (value "HECTOR_WATCH_1_TPTP20R")
      (footprint "eagle-import:HECTOR_WATCH_1_TP20R")
      (libsource (lib "eagle-import") (part "HECTOR_WATCH_1_TPTP20R"))
    )
    (comp (ref "TP_VREG")
      (value "HECTOR_WATCH_1_TPTP20R")
      (footprint "eagle-import:HECTOR_WATCH_1_TP20R")
      (libsource (lib "eagle-import") (part "HECTOR_WATCH_1_TPTP20R"))
    )
    (comp (ref "U1")
      (value "NRF52840_QF")
      (footprint "eagle-import:NORDIC_NRF_4_AQFN50P700X700X85_HS-74N")
      (libsource (lib "eagle-import") (part "NORDIC_NRF_4_NRF52840_QF"))
    )
    (comp (ref "U3")
      (value "MAX17048G+T10")
      (footprint "eagle-import:ESP32_C6_LIBRARY_SON50P200X200X80-9N")
      (fields (field (name "MF") "Analog Devices"))
      (libsource (lib "eagle-import") (part "ESP32_C6_LIBRARY_MAX17048G+T10"))
    )
    (comp (ref "X1")
      (value "32MHz")
      (footprint "eagle-import:NORDIC_NRF_BT-XTAL_2016_N")
      (libsource (lib "eagle-import") (part "NORDIC_NRF_XTAL_32MHZ"))
    )
    (comp (ref "X2")
      (value "32.768kHz")
      (footprint "eagle-import:NORDIC_NRF_1_XTAL_3215_N")
      (libsource (lib "eagle-import") (part "NORDIC_NRF_1_XTAL_32KHZ"))
    )
  )
  (nets
    (net (code "1") (name "3V3{slash}1.7D") (class "Default")
      (node (ref "C34") (pin "1") (pinfunction "1_1") (pintype "passive"))
      (node (ref "DMG2305UX-7") (pin "2") (pinfunction "S_2") (pintype "bidirectional"))
      (node (ref "IC2") (pin "C2") (pinfunction "VDD_C2") (pintype "bidirectional"))
      (node (ref "R5") (pin "2") (pinfunction "2_2") (pintype "bidirectional"))
      (node (ref "R7") (pin "2") (pinfunction "2_2") (pintype "bidirectional"))
      (node (ref "R8") (pin "2") (pinfunction "2_2") (pintype "bidirectional"))
      (node (ref "R_PWR_EPD") (pin "2") (pinfunction "2_2") (pintype "bidirectional"))
    )
    (net (code "2") (name "3V3{slash}2.4A") (class "Default")
      (node (ref "C12") (pin "1") (pinfunction "1_1") (pintype "passive"))
      (node (ref "C14") (pin "1") (pinfunction "1_1") (pintype "passive"))
      (node (ref "C19") (pin "1") (pinfunction "1_1") (pintype "passive"))
      (node (ref "C25") (pin "1") (pinfunction "1_1") (pintype "passive"))
      (node (ref "C33") (pin "1") (pinfunction "1_1") (pintype "passive"))
      (node (ref "C6") (pin "1") (pinfunction "1_1") (pintype "passive"))
      (node (ref "C7") (pin "1") (pinfunction "1_1") (pintype "passive"))
      (node (ref "C8") (pin "1") (pinfunction "1_1") (pintype "passive"))
      (node (ref "IC3") (pin "10") (pinfunction "CSB_10") (pintype "bidirectional"))
      (node (ref "IC3") (pin "3") (pinfunction "VDDIO_3") (pintype "bidirectional"))
      (node (ref "IC3") (pin "7") (pinfunction "VDD_7") (pintype "bidirectional"))
      (node (ref "IC9") (pin "E2") (pinfunction "VOUT_1_E2") (pintype "bidirectional"))
      (node (ref "IC9") (pin "E3") (pinfunction "VOUT_2_E3") (pintype "bidirectional"))
      (node (ref "J2") (pin "1") (pinfunction "1_1") (pintype "bidirectional"))
      (node (ref "R17") (pin "1") (pinfunction "1_1") (pintype "bidirectional"))
      (node (ref "R18") (pin "1") (pinfunction "1_1") (pintype "bidirectional"))
      (node (ref "TP_3.3V") (pin "TP") (pinfunction "TP_TP") (pintype "input"))
      (node (ref "TP_3V3") (pin "TP") (pinfunction "TP_TP") (pintype "input"))
      (node (ref "U1") (pin "P$A22") (pinfunction "VDD_P$A22") (pintype "power_in"))
      (node (ref "U1") (pin "P$AD14") (pinfunction "VDD_P$AD14") (pintype "power_in"))
      (node (ref "U1") (pin "P$AD23") (pinfunction "VDD_P$AD23") (pintype "power_in"))
      (node (ref "U1") (pin "P$B1") (pinfunction "VDD_P$B1") (pintype "power_in"))
      (node (ref "U1") (pin "P$W1") (pinfunction "VDD_P$W1") (pintype "power_in"))
      (node (ref "U1") (pin "P$Y2") (pinfunction "VDDH_P$Y2") (pintype "power_in"))
    )
    (net (code "3") (name "ALERT{slash}1.6C") (class "Default")
      (node (ref "U3") (pin "5") (pinfunction "~{ALERT}_5") (pintype "output"))
    )
    (net (code "4") (name "ALERT{slash}2.5C") (class "Default")
      (node (ref "U1") (pin "P$J24") (pinfunction "P0.10/NFC2_P$J24") (pintype "bidirectional"))
    )
    (net (code "5") (name "D+{slash}1.5D") (class "Default")
      (node (ref "D3") (pin "4") (pinfunction "I/O2_2_4") (pintype "bidirectional"))
    )
    (net (code "6") (name "D+{slash}2.7D") (class "Default")
      (node (ref "U1") (pin "P$AD6") (pinfunction "D+_P$AD6") (pintype "bidirectional"))
    )
    (net (code "7") (name "D-{slash}1.5D") (class "Default")
      (node (ref "D3") (pin "6") (pinfunction "I/O1_2_6") (pintype "bidirectional"))
    )
    (net (code "8") (name "D-{slash}2.7D") (class "Default")
      (node (ref "U1") (pin "P$AD4") (pinfunction "D-_P$AD4") (pintype "bidirectional"))
    )
    (net (code "9") (name "DN") (class "Default")
      (node (ref "D3") (pin "1") (pinfunction "I/O1_1_1") (pintype "bidirectional"))
      (node (ref "J4") (pin "A7") (pinfunction "DN1_A7") (pintype "bidirectional"))
      (node (ref "J4") (pin "B7") (pinfunction "DN2_B7") (pintype "bidirectional"))
    )
    (net (code "10") (name "DP") (class "Default")
      (node (ref "D3") (pin "3") (pinfunction "I/O2_1_3") (pintype "bidirectional"))
      (node (ref "J4") (pin "A6") (pinfunction "DP1_A6") (pintype "bidirectional"))
      (node (ref "J4") (pin "B6") (pinfunction "DP2_B6") (pintype "bidirectional"))
    )
    (net (code "11") (name "EPD_3V3") (class "Default")
      (node (ref "C1-EP-DR") (pin "1") (pinfunction "1_1") (pintype "passive"))
      (node (ref "DMG2305UX-7") (pin "3") (pinfunction "D_3") (pintype "bidirectional"))
      (node (ref "EPD_C5") (pin "2") (pinfunction "2_2") (pintype "passive"))
      (node (ref "J1") (pin "15") (pinfunction "15_15") (pintype "bidirectional"))
      (node (ref "J1") (pin "16") (pinfunction "16_16") (pintype "bidirectional"))
      (node (ref "L5") (pin "1") (pinfunction "1_1") (pintype "passive"))
    )
    (net (code "12") (name "EPD_BUSY{slash}1.5D") (class "Default")
      (node (ref "J1") (pin "9") (pinfunction "9_9") (pintype "bidirectional"))
    )
    (net (code "13") (name "EPD_BUSY{slash}2.2D") (class "Default")
      (node (ref "U1") (pin "P$AD12") (pinfunction "P0.17_P$AD12") (pintype "bidirectional"))
    )
    (net (code "14") (name "EPD_CS{slash}1.4C") (class "Default")
      (node (ref "J1") (pin "12") (pinfunction "12_12") (pintype "bidirectional"))
    )
    (net (code "15") (name "EPD_CS{slash}2.2D") (class "Default")
      (node (ref "U1") (pin "P$K2") (pinfunction "P0.05/AIN3_P$K2") (pintype "bidirectional"))
    )
    (net (code "16") (name "EPD_DC{slash}1.5D") (class "Default")
      (node (ref "J1") (pin "11") (pinfunction "11_11") (pintype "bidirectional"))
    )
    (net (code "17") (name "EPD_DC{slash}2.2D") (class "Default")
      (node (ref "U1") (pin "P$AD10") (pinfunction "P0.15_P$AD10") (pintype "bidirectional"))
    )
    (net (code "18") (name "EPD_RST{slash}1.5D") (class "Default")
      (node (ref "J1") (pin "10") (pinfunction "10_10") (pintype "bidirectional"))
    )
    (net (code "19") (name "EPD_RST{slash}2.2D") (class "Default")
      (node (ref "U1") (pin "P$AC11") (pinfunction "P0.16_P$AC11") (pintype "bidirectional"))
    )
    (net (code "20") (name "GDR") (class "Default")
      (node (ref "J1") (pin "2") (pinfunction "2_2") (pintype "bidirectional"))
      (node (ref "Q3") (pin "1") (pinfunction "G_1") (pintype "bidirectional"))
      (node (ref "R2_EP_DR") (pin "2") (pinfunction "2_2") (pintype "bidirectional"))
    )
    (net (code "21") (name "GND") (class "Default")
      (node (ref "C1") (pin "2") (pinfunction "2_2") (pintype "passive"))
      (node (ref "C1-EP-DR") (pin "2") (pinfunction "2_2") (pintype "passive"))
      (node (ref "C10") (pin "2") (pinfunction "2_2") (pintype "passive"))
      (node (ref "C11") (pin "2") (pinfunction "2_2") (pintype "passive"))
      (node (ref "C12") (pin "2") (pinfunction "2_2") (pintype "passive"))
      (node (ref "C13") (pin "2") (pinfunction "2_2") (pintype "passive"))
      (node (ref "C14") (pin "2") (pinfunction "2_2") (pintype "passive"))
      (node (ref "C15") (pin "2") (pinfunction "2_2") (pintype "passive"))
      (node (ref "C16") (pin "2") (pinfunction "2_2") (pintype "passive"))
      (node (ref "C17") (pin "1") (pinfunction "1_1") (pintype "passive"))
      (node (ref "C18") (pin "2") (pinfunction "2_2") (pintype "passive"))
      (node (ref "C19") (pin "2") (pinfunction "2_2") (pintype "passive"))
      (node (ref "C2") (pin "2") (pinfunction "2_2") (pintype "passive"))
      (node (ref "C20") (pin "2") (pinfunction "2_2") (pintype "passive"))
      (node (ref "C21") (pin "2") (pinfunction "2_2") (pintype "passive"))
      (node (ref "C22") (pin "2") (pinfunction "2_2") (pintype "passive"))
      (node (ref "C23") (pin "2") (pinfunction "2_2") (pintype "passive"))
      (node (ref "C24") (pin "1") (pinfunction "1_1") (pintype "passive"))
      (node (ref "C25") (pin "2") (pinfunction "2_2") (pintype "passive"))
      (node (ref "C29") (pin "1") (pinfunction "1_1") (pintype "passive"))
      (node (ref "C3") (pin "2") (pinfunction "2_2") (pintype "passive"))
      (node (ref "C30") (pin "1") (pinfunction "1_1") (pintype "passive"))
      (node (ref "C31") (pin "1") (pinfunction "1_1") (pintype "passive"))
      (node (ref "C32") (pin "1") (pinfunction "1_1") (pintype "passive"))
      (node (ref "C33") (pin "2") (pinfunction "2_2") (pintype "passive"))
      (node (ref "C34") (pin "2") (pinfunction "2_2") (pintype "passive"))
      (node (ref "C37") (pin "1") (pinfunction "1_1") (pintype "passive"))
      (node (ref "C38") (pin "1") (pinfunction "1_1") (pintype "passive"))
      (node (ref "C39") (pin "2") (pinfunction "2_2") (pintype "passive"))
      (node (ref "C4") (pin "2") (pinfunction "2_2") (pintype "passive"))
      (node (ref "C42") (pin "2") (pinfunction "2_2") (pintype "passive"))
      (node (ref "C43") (pin "2") (pinfunction "2_2") (pintype "passive"))
      (node (ref "C5") (pin "2") (pinfunction "2_2") (pintype "passive"))
      (node (ref "C6") (pin "2") (pinfunction "2_2") (pintype "passive"))
      (node (ref "C7") (pin "2") (pinfunction "2_2") (pintype "passive"))
      (node (ref "C8") (pin "2") (pinfunction "2_2") (pintype "passive"))
      (node (ref "C9") (pin "2") (pinfunction "2_2") (pintype "passive"))
      (node (ref "D3") (pin "2") (pinfunction "GND_2") (pintype "bidirectional"))
      (node (ref "D4") (pin "1") (pinfunction "K_1") (pintype "bidirectional"))
      (node (ref "EPD_C10") (pin "1") (pinfunction "1_1") (pintype "passive"))
      (node (ref "EPD_C11") (pin "1") (pinfunction "1_1") (pintype "passive"))
      (node (ref "EPD_C12") (pin "1") (pinfunction "1_1") (pintype "passive"))
      (node (ref "EPD_C5") (pin "1") (pinfunction "1_1") (pintype "passive"))
      (node (ref "EPD_C6") (pin "1") (pinfunction "1_1") (pintype "passive"))
      (node (ref "EPD_C7") (pin "1") (pinfunction "1_1") (pintype "passive"))
      (node (ref "EPD_C8") (pin "1") (pinfunction "1_1") (pintype "passive"))
      (node (ref "EPD_C9") (pin "1") (pinfunction "1_1") (pintype "passive"))
      (node (ref "IC1") (pin "D2") (pinfunction "GND_D2") (pintype "bidirectional"))
      (node (ref "IC2") (pin "B1") (pinfunction "IN/TRIG_B1") (pintype "bidirectional"))
      (node (ref "IC2") (pin "B3") (pinfunction "GND_B3") (pintype "bidirectional"))
      (node (ref "IC3") (pin "8") (pinfunction "GNDIO_8") (pintype "bidirectional"))
      (node (ref "IC3") (pin "9") (pinfunction "GND_9") (pintype "bidirectional"))
      (node (ref "IC9") (pin "B1") (pinfunction "VSEL_B1") (pintype "bidirectional"))
      (node (ref "IC9") (pin "C1") (pinfunction "AGND_C1") (pintype "bidirectional"))
      (node (ref "IC9") (pin "C2") (pinfunction "PGND_1_C2") (pintype "bidirectional"))
      (node (ref "IC9") (pin "C3") (pinfunction "PGND_2_C3") (pintype "bidirectional"))
      (node (ref "J1") (pin "17") (pinfunction "17_17") (pintype "bidirectional"))
      (node (ref "J1") (pin "8") (pinfunction "8_8") (pintype "bidirectional"))
      (node (ref "J1") (pin "MP1") (pinfunction "MP1_MP1") (pintype "bidirectional"))
      (node (ref "J2") (pin "3") (pinfunction "3_3") (pintype "bidirectional"))
      (node (ref "J2") (pin "5") (pinfunction "5_5") (pintype "bidirectional"))
      (node (ref "J4") (pin "A12_B1") (pinfunction "GND_A12_B1") (pintype "power_in"))
      (node (ref "J4") (pin "A1_B12") (pinfunction "GND_A1_B12") (pintype "power_in"))
      (node (ref "J4") (pin "SH1") (pinfunction "SHIELD_SH1") (pintype "passive"))
      (node (ref "J4") (pin "SH2") (pinfunction "SHIELD_SH2") (pintype "passive"))
      (node (ref "J4") (pin "SH3") (pinfunction "SHIELD_SH3") (pintype "passive"))
      (node (ref "J4") (pin "SH4") (pinfunction "SHIELD_SH4") (pintype "passive"))
      (node (ref "R1_USB") (pin "1") (pinfunction "1_1") (pintype "bidirectional"))
      (node (ref "R2_EP_DR") (pin "1") (pinfunction "1_1") (pintype "bidirectional"))
      (node (ref "R2_USB") (pin "2") (pinfunction "2_2") (pintype "bidirectional"))
      (node (ref "R3") (pin "1") (pinfunction "1_1") (pintype "bidirectional"))
      (node (ref "R9") (pin "1") (pinfunction "1_1") (pintype "bidirectional"))
      (node (ref "R_TYPE_SEL") (pin "1") (pinfunction "1_1") (pintype "bidirectional"))
      (node (ref "SJ1") (pin "1") (pinfunction "1_1") (pintype "passive"))
      (node (ref "SW_DN") (pin "1") (pinfunction "1_1") (pintype "passive"))
      (node (ref "SW_ENT") (pin "1") (pinfunction "1_1") (pintype "passive"))
      (node (ref "SW_UP") (pin "1") (pinfunction "1_1") (pintype "passive"))
      (node (ref "TP_BAT_GND") (pin "TP") (pinfunction "TP_TP") (pintype "input"))
      (node (ref "TP_GND") (pin "TP") (pinfunction "TP_TP") (pintype "input"))
      (node (ref "U1") (pin "P$74") (pinfunction "VSS_PAD_P$74") (pintype "bidirectional"))
      (node (ref "U1") (pin "P$75") (pinfunction "VSS_PAD_P$75") (pintype "bidirectional"))
      (node (ref "U1") (pin "P$76") (pinfunction "VSS_PAD_P$76") (pintype "bidirectional"))
      (node (ref "U1") (pin "P$77") (pinfunction "VSS_PAD_P$77") (pintype "bidirectional"))
      (node (ref "U1") (pin "P$78") (pinfunction "VSS_PAD_P$78") (pintype "bidirectional"))
      (node (ref "U1") (pin "P$79") (pinfunction "VSS_PAD_P$79") (pintype "bidirectional"))
      (node (ref "U1") (pin "P$80") (pinfunction "VSS_PAD_P$80") (pintype "bidirectional"))
      (node (ref "U1") (pin "P$81") (pinfunction "VSS_PAD_P$81") (pintype "bidirectional"))
      (node (ref "U1") (pin "P$82") (pinfunction "VSS_PAD_P$82") (pintype "bidirectional"))
      (node (ref "U1") (pin "P$83") (pinfunction "VSS_PAD_P$83") (pintype "bidirectional"))
      (node (ref "U1") (pin "P$84") (pinfunction "VSS_PAD_P$84") (pintype "bidirectional"))
      (node (ref "U1") (pin "P$85") (pinfunction "VSS_PAD_P$85") (pintype "bidirectional"))
      (node (ref "U1") (pin "P$86") (pinfunction "VSS_PAD_P$86") (pintype "bidirectional"))
      (node (ref "U1") (pin "P$87") (pinfunction "VSS_PAD_P$87") (pintype "bidirectional"))
      (node (ref "U1") (pin "P$88") (pinfunction "VSS_PAD_P$88") (pintype "bidirectional"))
      (node (ref "U1") (pin "P$89") (pinfunction "VSS_PAD_P$89") (pintype "bidirectional"))
      (node (ref "U1") (pin "P$90") (pinfunction "VSS_PAD_P$90") (pintype "bidirectional"))
      (node (ref "U1") (pin "P$B7") (pinfunction "VSS_P$B7") (pintype "power_in"))
      (node (ref "U1") (pin "P$F23") (pinfunction "VSS_PA_P$F23") (pintype "bidirectional"))
      (node (ref "U3") (pin "1") (pinfunction "CTG_1") (pintype "power_in"))
      (node (ref "U3") (pin "4") (pinfunction "GND_4") (pintype "power_in"))
      (node (ref "U3") (pin "6") (pinfunction "QSTRT_6") (pintype "input"))
      (node (ref "U3") (pin "9") (pinfunction "EP_9") (pintype "power_in"))
      (node (ref "X1") (pin "2") (pinfunction "2_2") (pintype "passive"))
      (node (ref "X1") (pin "4") (pinfunction "4_4") (pintype "passive"))
    )
    (net (code "22") (name "HAPTIC_EN{slash}1.4C") (class "Default")
      (node (ref "IC2") (pin "A1") (pinfunction "EN_A1") (pintype "bidirectional"))
    )
    (net (code "23") (name "HAPTIC_EN{slash}2.6A") (class "Default")
      (node (ref "U1") (pin "P$U1") (pinfunction "P0.12_P$U1") (pintype "bidirectional"))
    )
    (net (code "24") (name "IMU_INT1") (class "Default")
      (node (ref "U1") (pin "P$N1") (pinfunction "P0.08_P$N1") (pintype "bidirectional"))
    )
    (net (code "25") (name "IMU_INT2") (class "Default")
      (node (ref "U1") (pin "P$P2") (pinfunction "P1.08_P$P2") (pintype "bidirectional"))
    )
    (net (code "26") (name "LX1") (class "Default")
      (node (ref "IC9") (pin "B2") (pinfunction "SW1_1_B2") (pintype "bidirectional"))
      (node (ref "IC9") (pin "B3") (pinfunction "SW1_2_B3") (pintype "bidirectional"))
      (node (ref "L7") (pin "1") (pinfunction "1_1") (pintype "bidirectional"))
    )
    (net (code "27") (name "LX2") (class "Default")
      (node (ref "IC9") (pin "D2") (pinfunction "SW2_1_D2") (pintype "bidirectional"))
      (node (ref "IC9") (pin "D3") (pinfunction "SW2_2_D3") (pintype "bidirectional"))
      (node (ref "L7") (pin "2") (pinfunction "2_2") (pintype "bidirectional"))
    )
    (net (code "28") (name "MOSI{slash}1.5B") (class "Default")
      (node (ref "J1") (pin "14") (pinfunction "14_14") (pintype "bidirectional"))
    )
    (net (code "29") (name "MOSI{slash}2.2D") (class "Default")
      (node (ref "U1") (pin "P$B13") (pinfunction "P0.03/AIN1_P$B13") (pintype "bidirectional"))
    )
    (net (code "30") (name "MU_INT1") (class "Default")
      (node (ref "IC3") (pin "5") (pinfunction "INT1_5") (pintype "bidirectional"))
    )
    (net (code "31") (name "MU_INT2") (class "Default")
      (node (ref "IC3") (pin "6") (pinfunction "INT2_6") (pintype "bidirectional"))
    )
    (net (code "32") (name "Net-(ANT1-FEED)") (class "Default")
      (node (ref "ANT1") (pin "1") (pinfunction "FEED_1") (pintype "input"))
      (node (ref "C22") (pin "1") (pinfunction "1_1") (pintype "passive"))
      (node (ref "C4") (pin "1") (pinfunction "1_1") (pintype "passive"))
      (node (ref "L1") (pin "2") (pinfunction "2_2") (pintype "passive"))
    )
    (net (code "33") (name "Net-(C29-Pad2)") (class "Default")
      (node (ref "C29") (pin "2") (pinfunction "2_2") (pintype "passive"))
      (node (ref "R7") (pin "1") (pinfunction "1_1") (pintype "bidirectional"))
    )
    (net (code "34") (name "Net-(C31-Pad2)") (class "Default")
      (node (ref "C31") (pin "2") (pinfunction "2_2") (pintype "passive"))
      (node (ref "R8") (pin "1") (pinfunction "1_1") (pintype "bidirectional"))
    )
    (net (code "35") (name "Net-(D2-K)") (class "Default")
      (node (ref "C2-EP-DR") (pin "1") (pinfunction "1_1") (pintype "passive"))
      (node (ref "D2") (pin "1") (pinfunction "K_1") (pintype "bidirectional"))
      (node (ref "D4") (pin "2") (pinfunction "A_2") (pintype "bidirectional"))
    )
    (net (code "36") (name "Net-(D5-A)") (class "Default")
      (node (ref "C2-EP-DR") (pin "2") (pinfunction "2_2") (pintype "passive"))
      (node (ref "D5") (pin "2") (pinfunction "A_2") (pintype "bidirectional"))
      (node (ref "L5") (pin "2") (pinfunction "2_2") (pintype "passive"))
      (node (ref "Q3") (pin "3") (pinfunction "D_3") (pintype "bidirectional"))
    )
    (net (code "37") (name "Net-(EPD_C1-Pad2)") (class "Default")
      (node (ref "EPD_C1") (pin "2") (pinfunction "2_2") (pintype "passive"))
      (node (ref "J1") (pin "5") (pinfunction "5_5") (pintype "bidirectional"))
    )
    (net (code "38") (name "Net-(EPD_C2-Pad2)") (class "Default")
      (node (ref "EPD_C2") (pin "2") (pinfunction "2_2") (pintype "passive"))
      (node (ref "J1") (pin "4") (pinfunction "4_4") (pintype "bidirectional"))
    )
    (net (code "39") (name "Net-(EPD_C6-Pad2)") (class "Default")
      (node (ref "EPD_C6") (pin "2") (pinfunction "2_2") (pintype "passive"))
      (node (ref "J1") (pin "18") (pinfunction "18_18") (pintype "bidirectional"))
    )
    (net (code "40") (name "Net-(EPD_C7-Pad2)") (class "Default")
      (node (ref "EPD_C7") (pin "2") (pinfunction "2_2") (pintype "passive"))
      (node (ref "J1") (pin "19") (pinfunction "19_19") (pintype "bidirectional"))
    )
    (net (code "41") (name "Net-(EPD_C8-Pad2)") (class "Default")
      (node (ref "EPD_C8") (pin "2") (pinfunction "2_2") (pintype "passive"))
      (node (ref "J1") (pin "20") (pinfunction "20_20") (pintype "bidirectional"))
    )
    (net (code "42") (name "Net-(EPD_C10-Pad2)") (class "Default")
      (node (ref "EPD_C10") (pin "2") (pinfunction "2_2") (pintype "passive"))
      (node (ref "J1") (pin "22") (pinfunction "22_22") (pintype "bidirectional"))
    )
    (net (code "43") (name "Net-(EPD_C12-Pad2)") (class "Default")
      (node (ref "EPD_C12") (pin "2") (pinfunction "2_2") (pintype "passive"))
      (node (ref "J1") (pin "24") (pinfunction "24_24") (pintype "bidirectional"))
    )
    (net (code "44") (name "Net-(IC1-TS{slash}MR)") (class "Default")
      (node (ref "IC1") (pin "D1") (pinfunction "TS/MR_D1") (pintype "bidirectional"))
      (node (ref "R9") (pin "2") (pinfunction "2_2") (pintype "bidirectional"))
    )
    (net (code "45") (name "Net-(IC2-REG)") (class "Default")
      (node (ref "C32") (pin "2") (pinfunction "2_2") (pintype "passive"))
      (node (ref "IC2") (pin "A2") (pinfunction "REG_A2") (pintype "bidirectional"))
    )
    (net (code "46") (name "Net-(IC3-SDO)") (class "Default")
      (node (ref "IC3") (pin "1") (pinfunction "SDO_1") (pintype "bidirectional"))
      (node (ref "R3") (pin "2") (pinfunction "2_2") (pintype "bidirectional"))
    )
    (net (code "47") (name "Net-(IC9-SCL)") (class "Default")
      (node (ref "IC9") (pin "D1") (pinfunction "SCL_D1") (pintype "bidirectional"))
      (node (ref "R4") (pin "2") (pinfunction "2_2") (pintype "bidirectional"))
    )
    (net (code "48") (name "Net-(IC9-SDA)") (class "Default")
      (node (ref "IC9") (pin "E1") (pinfunction "SDA_E1") (pintype "bidirectional"))
      (node (ref "R2") (pin "2") (pinfunction "2_2") (pintype "bidirectional"))
    )
    (net (code "49") (name "Net-(J4-CC1)") (class "Default")
      (node (ref "J4") (pin "A5") (pinfunction "CC1_A5") (pintype "bidirectional"))
      (node (ref "R1_USB") (pin "2") (pinfunction "2_2") (pintype "bidirectional"))
    )
    (net (code "50") (name "Net-(J4-CC2)") (class "Default")
      (node (ref "J4") (pin "B5") (pinfunction "CC2_B5") (pintype "bidirectional"))
      (node (ref "R2_USB") (pin "1") (pinfunction "1_1") (pintype "bidirectional"))
    )
    (net (code "51") (name "Net-(L2-Pad2)") (class "Default")
      (node (ref "L2") (pin "2") (pinfunction "2_2") (pintype "passive"))
      (node (ref "L3") (pin "1") (pinfunction "1_1") (pintype "passive"))
    )
    (net (code "52") (name "Net-(R1_EP_DR-Pad1)") (class "Default")
      (node (ref "R1_EP_DR") (pin "1") (pinfunction "1_1") (pintype "bidirectional"))
      (node (ref "R_TYPE_SEL") (pin "2") (pinfunction "2_2") (pintype "bidirectional"))
      (node (ref "SJ1") (pin "2") (pinfunction "2_2") (pintype "passive"))
    )
    (net (code "53") (name "Net-(U1-ANT)") (class "Default")
      (node (ref "C3") (pin "1") (pinfunction "1_1") (pintype "passive"))
      (node (ref "L1") (pin "1") (pinfunction "1_1") (pintype "passive"))
      (node (ref "U1") (pin "P$H23") (pinfunction "ANT_P$H23") (pintype "bidirectional"))
    )
    (net (code "54") (name "Net-(U1-DCC)") (class "Default")
      (node (ref "L2") (pin "1") (pinfunction "1_1") (pintype "passive"))
      (node (ref "U1") (pin "P$B3") (pinfunction "DCC_P$B3") (pintype "output"))
    )
    (net (code "55") (name "Net-(U1-DEC1)") (class "Default")
      (node (ref "C5") (pin "1") (pinfunction "1_1") (pintype "passive"))
      (node (ref "U1") (pin "P$C1") (pinfunction "DEC1_P$C1") (pintype "power_in"))
    )
    (net (code "56") (name "Net-(U1-DEC2)") (class "Default")
      (node (ref "C13") (pin "1") (pinfunction "1_1") (pintype "passive"))
      (node (ref "U1") (pin "P$A18") (pinfunction "DEC2_P$A18") (pintype "bidirectional"))
    )
    (net (code "57") (name "Net-(U1-DEC3)") (class "Default")
      (node (ref "C11") (pin "1") (pinfunction "1_1") (pintype "passive"))
      (node (ref "U1") (pin "P$D23") (pinfunction "DEC3_P$D23") (pintype "bidirectional"))
    )
    (net (code "58") (name "Net-(U1-DEC3V3)") (class "Default")
      (node (ref "C20") (pin "1") (pinfunction "1_1") (pintype "passive"))
      (node (ref "U1") (pin "P$AC5") (pinfunction "DEC3V3_P$AC5") (pintype "bidirectional"))
    )
    (net (code "59") (name "Net-(U1-DEC4)") (class "Default")
      (node (ref "C10") (pin "1") (pinfunction "1_1") (pintype "passive"))
      (node (ref "C15") (pin "1") (pinfunction "1_1") (pintype "passive"))
      (node (ref "C16") (pin "1") (pinfunction "1_1") (pintype "passive"))
      (node (ref "L3") (pin "2") (pinfunction "2_2") (pintype "passive"))
      (node (ref "U1") (pin "P$B5") (pinfunction "DEC4_P$B5") (pintype "power_in"))
      (node (ref "U1") (pin "P$E24") (pinfunction "DEC6_P$E24") (pintype "bidirectional"))
    )
    (net (code "60") (name "Net-(U1-DEC5)") (class "Default")
      (node (ref "C9") (pin "1") (pinfunction "1_1") (pintype "passive"))
      (node (ref "U1") (pin "P$N24") (pinfunction "DEC5_P$N24") (pintype "bidirectional"))
    )
    (net (code "61") (name "Net-(U1-P0.00{slash}XL1)") (class "Default")
      (node (ref "C17") (pin "2") (pinfunction "2_2") (pintype "passive"))
      (node (ref "U1") (pin "P$D2") (pinfunction "P0.00/XL1_P$D2") (pintype "bidirectional"))
      (node (ref "X2") (pin "2") (pinfunction "2_2") (pintype "passive"))
    )
    (net (code "62") (name "Net-(U1-P0.01{slash}XL2)") (class "Default")
      (node (ref "C18") (pin "1") (pinfunction "1_1") (pintype "passive"))
      (node (ref "U1") (pin "P$F2") (pinfunction "P0.01/XL2_P$F2") (pintype "bidirectional"))
      (node (ref "X2") (pin "1") (pinfunction "1_1") (pintype "passive"))
    )
    (net (code "63") (name "Net-(U1-XC1)") (class "Default")
      (node (ref "C1") (pin "1") (pinfunction "1_1") (pintype "passive"))
      (node (ref "U1") (pin "P$B24") (pinfunction "XC1_P$B24") (pintype "input"))
      (node (ref "X1") (pin "1") (pinfunction "1_1") (pintype "passive"))
    )
    (net (code "64") (name "Net-(U1-XC2)") (class "Default")
      (node (ref "C2") (pin "1") (pinfunction "1_1") (pintype "passive"))
      (node (ref "U1") (pin "P$A23") (pinfunction "XC2_P$A23") (pintype "output"))
      (node (ref "X1") (pin "3") (pinfunction "3_3") (pintype "passive"))
    )
    (net (code "65") (name "OUT") (class "Default")
      (node (ref "IC2") (pin "C3") (pinfunction "OUT-_C3") (pintype "bidirectional"))
    )
    (net (code "66") (name "OUT+") (class "Default")
      (node (ref "IC2") (pin "A3") (pinfunction "OUT+_A3") (pintype "bidirectional"))
      (node (ref "TP_OP") (pin "TP") (pinfunction "TP_TP") (pintype "input"))
    )
    (net (code "67") (name "OUT-") (class "Default")
      (node (ref "TP_ON") (pin "TP") (pinfunction "TP_TP") (pintype "input"))
    )
    (net (code "68") (name "P0.04") (class "Default")
      (node (ref "U1") (pin "P$J1") (pinfunction "P0.04/AIN2_P$J1") (pintype "bidirectional"))
    )
    (net (code "69") (name "P0.09") (class "Default")
      (node (ref "U1") (pin "P$L24") (pinfunction "P0.09/NFC1_P$L24") (pintype "bidirectional"))
    )
    (net (code "70") (name "P0.13{slash}1.5D") (class "Default")
      (node (ref "C30") (pin "2") (pinfunction "2_2") (pintype "passive"))
      (node (ref "R5") (pin "1") (pinfunction "1_1") (pintype "bidirectional"))
      (node (ref "SW_UP") (pin "2") (pinfunction "2_2") (pintype "passive"))
    )
    (net (code "71") (name "P0.13{slash}2.6C") (class "Default")
      (node (ref "U1") (pin "P$AD8") (pinfunction "P0.13_P$AD8") (pintype "bidirectional"))
    )
    (net (code "72") (name "P0.14{slash}1.5D") (class "Default")
      (node (ref "SW_ENT") (pin "2") (pinfunction "2_2") (pintype "passive"))
    )
    (net (code "73") (name "P0.14{slash}2.7C") (class "Default")
      (node (ref "U1") (pin "P$AC9") (pinfunction "P0.14_P$AC9") (pintype "bidirectional"))
    )
    (net (code "74") (name "P0.19") (class "Default")
      (node (ref "U1") (pin "P$AC15") (pinfunction "P0.19_P$AC15") (pintype "bidirectional"))
    )
    (net (code "75") (name "P0.20") (class "Default")
      (node (ref "U1") (pin "P$AD16") (pinfunction "P0.20_P$AD16") (pintype "bidirectional"))
    )
    (net (code "76") (name "P0.21") (class "Default")
      (node (ref "U1") (pin "P$AC17") (pinfunction "P0.21_P$AC17") (pintype "bidirectional"))
    )
    (net (code "77") (name "P0.22") (class "Default")
      (node (ref "U1") (pin "P$AD18") (pinfunction "P0.22_P$AD18") (pintype "bidirectional"))
    )
    (net (code "78") (name "P0.23") (class "Default")
      (node (ref "U1") (pin "P$AC19") (pinfunction "P0.23_P$AC19") (pintype "bidirectional"))
    )
    (net (code "79") (name "P0.24") (class "Default")
      (node (ref "U1") (pin "P$AD20") (pinfunction "P0.24_P$AD20") (pintype "bidirectional"))
    )
    (net (code "80") (name "P0.25") (class "Default")
      (node (ref "U1") (pin "P$AC21") (pinfunction "P0.25_P$AC21") (pintype "bidirectional"))
    )
    (net (code "81") (name "P0.26") (class "Default")
      (node (ref "U1") (pin "P$G1") (pinfunction "P0.26_P$G1") (pintype "bidirectional"))
    )
    (net (code "82") (name "P0.27") (class "Default")
      (node (ref "U1") (pin "P$H2") (pinfunction "P0.27_P$H2") (pintype "bidirectional"))
    )
    (net (code "83") (name "P0.28") (class "Default")
      (node (ref "U1") (pin "P$B11") (pinfunction "P0.28/AIN4_P$B11") (pintype "bidirectional"))
    )
    (net (code "84") (name "P0.29") (class "Default")
      (node (ref "U1") (pin "P$A10") (pinfunction "P0.29/AIN5_P$A10") (pintype "bidirectional"))
    )
    (net (code "85") (name "P0.30") (class "Default")
      (node (ref "U1") (pin "P$B9") (pinfunction "P0.30/AIN6_P$B9") (pintype "bidirectional"))
    )
    (net (code "86") (name "P0.31") (class "Default")
      (node (ref "U1") (pin "P$A8") (pinfunction "P0.31/AIN7_P$A8") (pintype "bidirectional"))
    )
    (net (code "87") (name "P1.01{slash}1.6C") (class "Default")
      (node (ref "DMG2305UX-7") (pin "1") (pinfunction "G_1") (pintype "bidirectional"))
      (node (ref "R_PWR_EPD") (pin "1") (pinfunction "1_1") (pintype "bidirectional"))
    )
    (net (code "88") (name "P1.01{slash}2.4B") (class "Default")
      (node (ref "U1") (pin "P$Y23") (pinfunction "P1.01_P$Y23") (pintype "bidirectional"))
    )
    (net (code "89") (name "P1.02{slash}1.6C") (class "Default")
      (node (ref "SW_DN") (pin "2") (pinfunction "2_2") (pintype "passive"))
    )
    (net (code "90") (name "P1.02{slash}2.8C") (class "Default")
      (node (ref "U1") (pin "P$W24") (pinfunction "P1.02_P$W24") (pintype "bidirectional"))
    )
    (net (code "91") (name "P1.03") (class "Default")
      (node (ref "U1") (pin "P$V23") (pinfunction "P1.03_P$V23") (pintype "bidirectional"))
    )
    (net (code "92") (name "P1.04") (class "Default")
      (node (ref "U1") (pin "P$U24") (pinfunction "P1.04_P$U24") (pintype "bidirectional"))
    )
    (net (code "93") (name "P1.05") (class "Default")
      (node (ref "U1") (pin "P$T23") (pinfunction "P1.05_P$T23") (pintype "bidirectional"))
    )
    (net (code "94") (name "P1.06") (class "Default")
      (node (ref "U1") (pin "P$R24") (pinfunction "P1.06_P$R24") (pintype "bidirectional"))
    )
    (net (code "95") (name "P1.07") (class "Default")
      (node (ref "U1") (pin "P$P23") (pinfunction "P1.07_P$P23") (pintype "bidirectional"))
    )
    (net (code "96") (name "P1.09") (class "Default")
      (node (ref "U1") (pin "P$R1") (pinfunction "P1.09_P$R1") (pintype "bidirectional"))
    )
    (net (code "97") (name "P1.10") (class "Default")
      (node (ref "U1") (pin "P$A20") (pinfunction "P1.10_P$A20") (pintype "bidirectional"))
    )
    (net (code "98") (name "P1.11") (class "Default")
      (node (ref "U1") (pin "P$B19") (pinfunction "P1.11_P$B19") (pintype "bidirectional"))
    )
    (net (code "99") (name "P1.12") (class "Default")
      (node (ref "U1") (pin "P$B17") (pinfunction "P1.12_P$B17") (pintype "bidirectional"))
    )
    (net (code "100") (name "P1.13") (class "Default")
      (node (ref "U1") (pin "P$A16") (pinfunction "P1.13_P$A16") (pintype "bidirectional"))
    )
    (net (code "101") (name "P1.14") (class "Default")
      (node (ref "U1") (pin "P$B15") (pinfunction "P1.14_P$B15") (pintype "bidirectional"))
    )
    (net (code "102") (name "P1.15") (class "Default")
      (node (ref "U1") (pin "P$A14") (pinfunction "P1.15_P$A14") (pintype "bidirectional"))
    )
    (net (code "103") (name "PMIC_INT") (class "Default")
      (node (ref "IC1") (pin "A1") (pinfunction "~{INT}_A1") (pintype "bidirectional"))
      (node (ref "U1") (pin "P$T2") (pinfunction "P0.11_P$T2") (pintype "bidirectional"))
    )
    (net (code "104") (name "PREVGH") (class "Default")
      (node (ref "D5") (pin "1") (pinfunction "K_1") (pintype "bidirectional"))
      (node (ref "EPD_C9") (pin "2") (pinfunction "2_2") (pintype "passive"))
      (node (ref "J1") (pin "21") (pinfunction "21_21") (pintype "bidirectional"))
    )
    (net (code "105") (name "PREVGL") (class "Default")
      (node (ref "D2") (pin "2") (pinfunction "A_2") (pintype "bidirectional"))
      (node (ref "EPD_C11") (pin "2") (pinfunction "2_2") (pintype "passive"))
      (node (ref "J1") (pin "23") (pinfunction "23_23") (pintype "bidirectional"))
    )
    (net (code "106") (name "RESE") (class "Default")
      (node (ref "J1") (pin "3") (pinfunction "3_3") (pintype "bidirectional"))
      (node (ref "Q3") (pin "2") (pinfunction "S_2") (pintype "bidirectional"))
      (node (ref "R1_EP_DR") (pin "2") (pinfunction "2_2") (pintype "bidirectional"))
    )
    (net (code "107") (name "RESET") (class "Default")
      (node (ref "J2") (pin "6") (pinfunction "6_6") (pintype "bidirectional"))
      (node (ref "TP_RESET") (pin "TP") (pinfunction "TP_TP") (pintype "input"))
      (node (ref "U1") (pin "P$AC13") (pinfunction "P0.18/RESET_P$AC13") (pintype "bidirectional"))
    )
    (net (code "108") (name "SCK{slash}1.5B") (class "Default")
      (node (ref "J1") (pin "13") (pinfunction "13_13") (pintype "bidirectional"))
    )
    (net (code "109") (name "SCK{slash}2.2D") (class "Default")
      (node (ref "U1") (pin "P$A12") (pinfunction "P0.02/AIN0_P$A12") (pintype "bidirectional"))
    )
    (net (code "110") (name "SCL{slash}1.4C") (class "Default")
      (node (ref "IC2") (pin "C1") (pinfunction "SCL_C1") (pintype "bidirectional"))
      (node (ref "U3") (pin "7") (pinfunction "SCL_7") (pintype "input"))
    )
    (net (code "111") (name "SCL{slash}2.4C") (class "Default")
      (node (ref "IC1") (pin "B1") (pinfunction "SCL_B1") (pintype "bidirectional"))
      (node (ref "IC3") (pin "12") (pinfunction "SCX_12") (pintype "bidirectional"))
      (node (ref "R17") (pin "2") (pinfunction "2_2") (pintype "bidirectional"))
      (node (ref "R4") (pin "1") (pinfunction "1_1") (pintype "bidirectional"))
      (node (ref "TP_SCL") (pin "TP") (pinfunction "TP_TP") (pintype "input"))
      (node (ref "U1") (pin "P$M2") (pinfunction "P0.07_P$M2") (pintype "bidirectional"))
    )
    (net (code "112") (name "SDA{slash}1.4C") (class "Default")
      (node (ref "IC2") (pin "B2") (pinfunction "SDA_B2") (pintype "bidirectional"))
      (node (ref "U3") (pin "8") (pinfunction "SDA_8") (pintype "bidirectional"))
    )
    (net (code "113") (name "SDA{slash}2.4C") (class "Default")
      (node (ref "IC1") (pin "C1") (pinfunction "SDA_C1") (pintype "bidirectional"))
      (node (ref "IC3") (pin "2") (pinfunction "SDX_2") (pintype "bidirectional"))
      (node (ref "R18") (pin "2") (pinfunction "2_2") (pintype "bidirectional"))
      (node (ref "R2") (pin "1") (pinfunction "1_1") (pintype "bidirectional"))
      (node (ref "TP_SDA") (pin "TP") (pinfunction "TP_TP") (pintype "input"))
      (node (ref "U1") (pin "P$L1") (pinfunction "P0.06_P$L1") (pintype "bidirectional"))
    )
    (net (code "114") (name "SWDCLK") (class "Default")
      (node (ref "J2") (pin "4") (pinfunction "4_4") (pintype "bidirectional"))
      (node (ref "TP_SWDCLK") (pin "TP") (pinfunction "TP_TP") (pintype "input"))
      (node (ref "U1") (pin "P$AA24") (pinfunction "SWDCLK_P$AA24") (pintype "input"))
    )
    (net (code "115") (name "SWDIO") (class "Default")
      (node (ref "J2") (pin "2") (pinfunction "2_2") (pintype "bidirectional"))
      (node (ref "TP_SWDIO") (pin "TP") (pinfunction "TP_TP") (pintype "input"))
      (node (ref "U1") (pin "P$AC24") (pinfunction "SWDIO_P$AC24") (pintype "bidirectional"))
    )
    (net (code "116") (name "SWO") (class "Default")
      (node (ref "TP_SWO") (pin "TP") (pinfunction "TP_TP") (pintype "input"))
      (node (ref "U1") (pin "P$AD22") (pinfunction "P1.00_P$AD22") (pintype "bidirectional"))
    )
    (net (code "117") (name "VBAT{slash}1.2A") (class "Default")
      (node (ref "C27") (pin "2") (pinfunction "2_2") (pintype "passive"))
      (node (ref "TP_VBAT") (pin "TP") (pinfunction "TP_TP") (pintype "input"))
      (node (ref "U3") (pin "2") (pinfunction "CELL_2") (pintype "power_in"))
      (node (ref "U3") (pin "3") (pinfunction "VDD_3") (pintype "power_in"))
    )
    (net (code "118") (name "VBAT{slash}2.5C") (class "Default")
      (node (ref "C37") (pin "2") (pinfunction "2_2") (pintype "passive"))
      (node (ref "IC1") (pin "C2") (pinfunction "BAT_C2") (pintype "bidirectional"))
    )
    (net (code "119") (name "VBUS{slash}1.5D") (class "Default")
      (node (ref "C42") (pin "1") (pinfunction "1_1") (pintype "passive"))
      (node (ref "C43") (pin "1") (pinfunction "1_1") (pintype "passive"))
      (node (ref "D3") (pin "5") (pinfunction "VBUS_5") (pintype "bidirectional"))
      (node (ref "J4") (pin "A4_B9") (pinfunction "VBUS_A4_B9") (pintype "power_in"))
      (node (ref "J4") (pin "A9_B4") (pinfunction "VBUS_A9_B4") (pintype "power_in"))
    )
    (net (code "120") (name "VBUS{slash}2.6D") (class "Default")
      (node (ref "C21") (pin "1") (pinfunction "1_1") (pintype "passive"))
      (node (ref "C38") (pin "2") (pinfunction "2_2") (pintype "passive"))
      (node (ref "IC1") (pin "A2") (pinfunction "IN_A2") (pintype "bidirectional"))
      (node (ref "U1") (pin "P$AD2") (pinfunction "VBUS_P$AD2") (pintype "power_in"))
    )
    (net (code "121") (name "VREG") (class "Default")
      (node (ref "C23") (pin "1") (pinfunction "1_1") (pintype "passive"))
      (node (ref "C24") (pin "2") (pinfunction "2_2") (pintype "passive"))
      (node (ref "C39") (pin "1") (pinfunction "1_1") (pintype "passive"))
      (node (ref "IC1") (pin "B2") (pinfunction "SYS_B2") (pintype "bidirectional"))
      (node (ref "IC9") (pin "A1") (pinfunction "EN_A1") (pintype "bidirectional"))
      (node (ref "IC9") (pin "A2") (pinfunction "VIN_1_A2") (pintype "bidirectional"))
      (node (ref "IC9") (pin "A3") (pinfunction "VIN_2_A3") (pintype "bidirectional"))
      (node (ref "TP_VREG") (pin "TP") (pinfunction "TP_TP") (pintype "input"))
    )
    (net (code "122") (name "unconnected-(ANT1-NC-Pad2)") (class "Default")
      (node (ref "ANT1") (pin "2") (pinfunction "NC_2") (pintype "no_connect"))
    )
    (net (code "123") (name "unconnected-(C27-Pad1)") (class "Default")
      (node (ref "C27") (pin "1") (pinfunction "1_1") (pintype "passive"))
    )
    (net (code "124") (name "unconnected-(EPD_C1-Pad1)") (class "Default")
      (node (ref "EPD_C1") (pin "1") (pinfunction "1_1") (pintype "passive"))
    )
    (net (code "125") (name "unconnected-(EPD_C2-Pad1)") (class "Default")
      (node (ref "EPD_C2") (pin "1") (pinfunction "1_1") (pintype "passive"))
    )
    (net (code "126") (name "unconnected-(IC3-ASCL-Pad11)") (class "Default")
      (node (ref "IC3") (pin "11") (pinfunction "ASCL_11") (pintype "bidirectional"))
    )
    (net (code "127") (name "unconnected-(IC3-ASDA-Pad4)") (class "Default")
      (node (ref "IC3") (pin "4") (pinfunction "ASDA_4") (pintype "bidirectional"))
    )
    (net (code "128") (name "unconnected-(J1-Pad1)") (class "Default")
      (node (ref "J1") (pin "1") (pinfunction "1_1") (pintype "bidirectional"))
    )
    (net (code "129") (name "unconnected-(J1-Pad6)") (class "Default")
      (node (ref "J1") (pin "6") (pinfunction "6_6") (pintype "bidirectional"))
    )
    (net (code "130") (name "unconnected-(J1-Pad7)") (class "Default")
      (node (ref "J1") (pin "7") (pinfunction "7_7") (pintype "bidirectional"))
    )
    (net (code "131") (name "unconnected-(J1-PadMP2)") (class "Default")
      (node (ref "J1") (pin "MP2") (pinfunction "MP2_MP2") (pintype "bidirectional"))
    )
    (net (code "132") (name "unconnected-(J4-SBU1-PadA8)") (class "Default")
      (node (ref "J4") (pin "A8") (pinfunction "SBU1_A8") (pintype "bidirectional"))
    )
    (net (code "133") (name "unconnected-(J4-SBU2-PadB8)") (class "Default")
      (node (ref "J4") (pin "B8") (pinfunction "SBU2_B8") (pintype "bidirectional"))
    )
    (net (code "134") (name "unconnected-(U1-DCCH-PadP$AB2)") (class "Default")
      (node (ref "U1") (pin "P$AB2") (pinfunction "DCCH_P$AB2") (pintype "bidirectional"))
    )
  )
)
